# Sheet_MP.net
KiCad netlist of a schematic drawn in Altium Designer
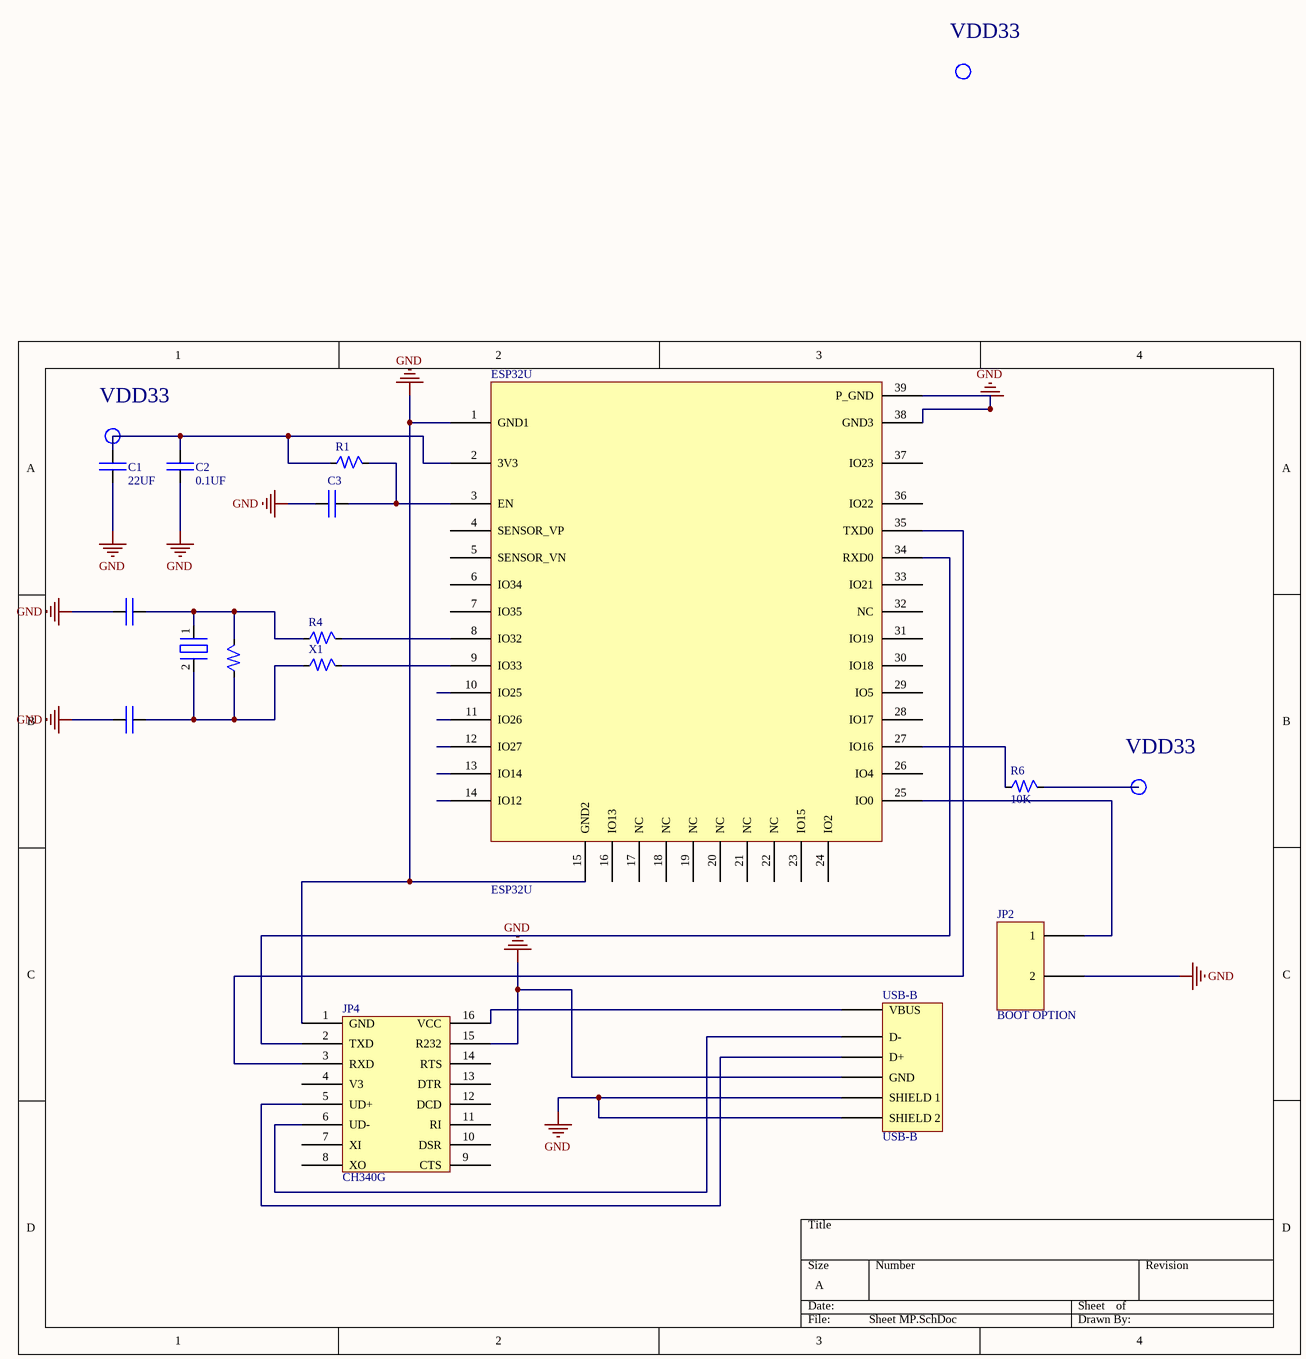
[diagram p0: Sheet MP.SchDoc]

(export (version "E")
  (design (tool "Eeschema 10.0.6"))
  (components
    (comp (ref "C1")
      (value "22UF")
      (footprint "Capacitor")
      (fields (field (name "MANUFACTURER") "PANASONIC") (field (name "MANUFACTURER PART") "EEHZA1V470P"))
      (libsource (lib "SchlibMP") (part "CAP"))
    )
    (comp (ref "C2")
      (value "0.1UF")
      (footprint "Capacitor")
      (fields (field (name "MANUFACTURER") "PANASONIC") (field (name "MANUFACTURER PART") "EEHZA1V470P"))
      (libsource (lib "SchlibMP") (part "CAP"))
    )
    (comp (ref "C3")
      (value "CAP")
      (footprint "Capacitor")
      (fields (field (name "MANUFACTURER") "PANASONIC") (field (name "MANUFACTURER PART") "EEHZA1V470P"))
      (libsource (lib "SchlibMP") (part "CAP"))
    )
    (comp (ref "C4")
      (value "CAP")
      (footprint "Capacitor")
      (fields (field (name "MANUFACTURER") "PANASONIC") (field (name "MANUFACTURER PART") "EEHZA1V470P"))
      (libsource (lib "SchlibMP") (part "CAP"))
    )
    (comp (ref "C5")
      (value "CAP")
      (footprint "Capacitor")
      (fields (field (name "MANUFACTURER") "PANASONIC") (field (name "MANUFACTURER PART") "EEHZA1V470P"))
      (libsource (lib "SchlibMP") (part "CAP"))
    )
    (comp (ref "ESP32U")
      (value "ESP32U")
      (footprint "ESP32U")
      (fields (field (name "MANUFACTURER") "Ai-Thinker") (field (name "MANUFACTURER PART") "ESP32-S"))
      (libsource (lib "SchlibMP") (part "ESP32U"))
    )
    (comp (ref "JP2")
      (value "BOOT OPTION")
      (footprint "HEADER 2 PINS - duplicate")
      (fields
        (field (name "MANUFACTURER") "JST Sales America Inc.")
        (field (name "MANUFACTURER PART") "B2B-XH-A")
      )
      (libsource (lib "SchlibMP") (part "HEADER 2 PINS"))
    )
    (comp (ref "JP4")
      (value "CH340G")
      (footprint "CH340G - duplicate1")
      (fields (field (name "MANUFACTURER") "WCH"))
      (libsource (lib "SchlibMP") (part "CH340G"))
    )
    (comp (ref "R1")
      (value "0805")
      (footprint "Resistor")
      (fields (field (name "MANUFACTURER") "YAGEO") (field (name "MANUFACTURER PART") "RC0805FR-0710KL"))
      (libsource (lib "SchlibMP") (part "0805"))
    )
    (comp (ref "R4")
      (value "0805")
      (footprint "Resistor")
      (fields (field (name "MANUFACTURER") "YAGEO") (field (name "MANUFACTURER PART") "RC0805FR-0710KL"))
      (libsource (lib "SchlibMP") (part "0805"))
    )
    (comp (ref "R5")
      (value "0805")
      (footprint "Resistor")
      (fields (field (name "MANUFACTURER") "YAGEO") (field (name "MANUFACTURER PART") "RC0805FR-0710KL"))
      (libsource (lib "SchlibMP") (part "0805"))
    )
    (comp (ref "R6")
      (value "10K")
      (footprint "Resistor")
      (fields (field (name "MANUFACTURER") "YAGEO") (field (name "MANUFACTURER PART") "RC0805FR-0710KL"))
      (libsource (lib "SchlibMP") (part "0805"))
    )
    (comp (ref "T1")
      (value "CRYSTAL")
      (footprint "CRYSTAL")
      (fields (field (name "MANUFACTURER") "EPSON") (field (name "MANUFACTURER PART") "Q13FC13500004"))
      (libsource (lib "SchlibMP") (part "CRYSTAL"))
    )
    (comp (ref "USB-B")
      (value "USB-B")
      (footprint "USB-B - duplicate1")
      (fields (field (name "MANUFACTURER") "Switchcraft Inc.") (field (name "MANUFACTURER PART") "RAHUB20"))
      (libsource (lib "SchlibMP") (part "USB-B"))
    )
    (comp (ref "X1")
      (value "0805")
      (footprint "Resistor")
      (fields (field (name "MANUFACTURER") "YAGEO") (field (name "MANUFACTURER PART") "RC0805FR-0710KL"))
      (libsource (lib "SchlibMP") (part "0805"))
    )
  )
  (nets
    (net (code "1") (name "GND") (class "Default")
      (node (ref "C1") (pin "1") (pinfunction "1_1") (pintype "passive"))
      (node (ref "C2") (pin "1") (pinfunction "1_1") (pintype "passive"))
      (node (ref "C3") (pin "2") (pinfunction "2_2") (pintype "passive"))
      (node (ref "C4") (pin "2") (pinfunction "2_2") (pintype "passive"))
      (node (ref "C5") (pin "2") (pinfunction "2_2") (pintype "passive"))
      (node (ref "ESP32U") (pin "1") (pinfunction "GND1_1") (pintype "passive"))
      (node (ref "ESP32U") (pin "15") (pinfunction "GND2_15") (pintype "passive"))
      (node (ref "ESP32U") (pin "38") (pinfunction "GND3_38") (pintype "passive"))
      (node (ref "ESP32U") (pin "39") (pinfunction "P_GND_39") (pintype "passive"))
      (node (ref "JP2") (pin "2") (pinfunction "2_2") (pintype "passive"))
      (node (ref "JP4") (pin "1") (pinfunction "GND_1") (pintype "passive"))
      (node (ref "JP4") (pin "15") (pinfunction "R232_15") (pintype "passive"))
      (node (ref "USB-B") (pin "4") (pinfunction "GND_4") (pintype "passive"))
      (node (ref "USB-B") (pin "5") (pinfunction "SHIELD_1_5") (pintype "passive"))
      (node (ref "USB-B") (pin "6") (pinfunction "SHIELD_2_6") (pintype "passive"))
    )
    (net (code "2") (name "Net-(C4-Pad1)") (class "Default")
      (node (ref "C4") (pin "1") (pinfunction "1_1") (pintype "passive"))
      (node (ref "R5") (pin "1") (pinfunction "1_1") (pintype "passive"))
      (node (ref "T1") (pin "2") (pinfunction "2_2") (pintype "passive"))
      (node (ref "X1") (pin "1") (pinfunction "1_1") (pintype "passive"))
    )
    (net (code "3") (name "Net-(C5-Pad1)") (class "Default")
      (node (ref "C5") (pin "1") (pinfunction "1_1") (pintype "passive"))
      (node (ref "R4") (pin "1") (pinfunction "1_1") (pintype "passive"))
      (node (ref "R5") (pin "2") (pinfunction "2_2") (pintype "passive"))
      (node (ref "T1") (pin "1") (pinfunction "1_1") (pintype "passive"))
    )
    (net (code "4") (name "Net-(ESP32U-3V3)") (class "Default")
      (node (ref "C1") (pin "2") (pinfunction "2_2") (pintype "passive"))
      (node (ref "C2") (pin "2") (pinfunction "2_2") (pintype "passive"))
      (node (ref "ESP32U") (pin "2") (pinfunction "3V3_2") (pintype "passive"))
      (node (ref "R1") (pin "1") (pinfunction "1_1") (pintype "passive"))
    )
    (net (code "5") (name "Net-(ESP32U-EN)") (class "Default")
      (node (ref "C3") (pin "1") (pinfunction "1_1") (pintype "passive"))
      (node (ref "ESP32U") (pin "3") (pinfunction "EN_3") (pintype "passive"))
      (node (ref "R1") (pin "2") (pinfunction "2_2") (pintype "passive"))
    )
    (net (code "6") (name "Net-(ESP32U-IO0)") (class "Default")
      (node (ref "ESP32U") (pin "25") (pinfunction "IO0_25") (pintype "passive"))
      (node (ref "JP2") (pin "1") (pinfunction "1_1") (pintype "passive"))
    )
    (net (code "7") (name "Net-(ESP32U-IO16)") (class "Default")
      (node (ref "ESP32U") (pin "27") (pinfunction "IO16_27") (pintype "passive"))
      (node (ref "R6") (pin "1") (pinfunction "1_1") (pintype "passive"))
    )
    (net (code "8") (name "Net-(ESP32U-IO32)") (class "Default")
      (node (ref "ESP32U") (pin "8") (pinfunction "IO32_8") (pintype "passive"))
      (node (ref "R4") (pin "2") (pinfunction "2_2") (pintype "passive"))
    )
    (net (code "9") (name "Net-(ESP32U-IO33)") (class "Default")
      (node (ref "ESP32U") (pin "9") (pinfunction "IO33_9") (pintype "passive"))
      (node (ref "X1") (pin "2") (pinfunction "2_2") (pintype "passive"))
    )
    (net (code "10") (name "Net-(ESP32U-RXD0)") (class "Default")
      (node (ref "ESP32U") (pin "34") (pinfunction "RXD0_34") (pintype "passive"))
      (node (ref "JP4") (pin "2") (pinfunction "TXD_2") (pintype "passive"))
    )
    (net (code "11") (name "Net-(ESP32U-TXD0)") (class "Default")
      (node (ref "ESP32U") (pin "35") (pinfunction "TXD0_35") (pintype "passive"))
      (node (ref "JP4") (pin "3") (pinfunction "RXD_3") (pintype "passive"))
    )
    (net (code "12") (name "Net-(JP4-UD+)") (class "Default")
      (node (ref "JP4") (pin "5") (pinfunction "UD+_5") (pintype "passive"))
      (node (ref "USB-B") (pin "3") (pinfunction "D+_3") (pintype "passive"))
    )
    (net (code "13") (name "Net-(JP4-UD-)") (class "Default")
      (node (ref "JP4") (pin "6") (pinfunction "UD-_6") (pintype "passive"))
      (node (ref "USB-B") (pin "2") (pinfunction "D-_2") (pintype "passive"))
    )
    (net (code "14") (name "Net-(JP4-VCC)") (class "Default")
      (node (ref "JP4") (pin "16") (pinfunction "VCC_16") (pintype "passive"))
      (node (ref "USB-B") (pin "1") (pinfunction "VBUS_1") (pintype "passive"))
    )
    (net (code "15") (name "unconnected-(ESP32U-IO2-Pad24)") (class "Default")
      (node (ref "ESP32U") (pin "24") (pinfunction "IO2_24") (pintype "passive"))
    )
    (net (code "16") (name "unconnected-(ESP32U-IO4-Pad26)") (class "Default")
      (node (ref "ESP32U") (pin "26") (pinfunction "IO4_26") (pintype "passive"))
    )
    (net (code "17") (name "unconnected-(ESP32U-IO5-Pad29)") (class "Default")
      (node (ref "ESP32U") (pin "29") (pinfunction "IO5_29") (pintype "passive"))
    )
    (net (code "18") (name "unconnected-(ESP32U-IO12-Pad14)") (class "Default")
      (node (ref "ESP32U") (pin "14") (pinfunction "IO12_14") (pintype "passive"))
    )
    (net (code "19") (name "unconnected-(ESP32U-IO13-Pad16)") (class "Default")
      (node (ref "ESP32U") (pin "16") (pinfunction "IO13_16") (pintype "passive"))
    )
    (net (code "20") (name "unconnected-(ESP32U-IO14-Pad13)") (class "Default")
      (node (ref "ESP32U") (pin "13") (pinfunction "IO14_13") (pintype "passive"))
    )
    (net (code "21") (name "unconnected-(ESP32U-IO15-Pad23)") (class "Default")
      (node (ref "ESP32U") (pin "23") (pinfunction "IO15_23") (pintype "passive"))
    )
    (net (code "22") (name "unconnected-(ESP32U-IO17-Pad28)") (class "Default")
      (node (ref "ESP32U") (pin "28") (pinfunction "IO17_28") (pintype "passive"))
    )
    (net (code "23") (name "unconnected-(ESP32U-IO18-Pad30)") (class "Default")
      (node (ref "ESP32U") (pin "30") (pinfunction "IO18_30") (pintype "passive"))
    )
    (net (code "24") (name "unconnected-(ESP32U-IO19-Pad31)") (class "Default")
      (node (ref "ESP32U") (pin "31") (pinfunction "IO19_31") (pintype "passive"))
    )
    (net (code "25") (name "unconnected-(ESP32U-IO21-Pad33)") (class "Default")
      (node (ref "ESP32U") (pin "33") (pinfunction "IO21_33") (pintype "passive"))
    )
    (net (code "26") (name "unconnected-(ESP32U-IO22-Pad36)") (class "Default")
      (node (ref "ESP32U") (pin "36") (pinfunction "IO22_36") (pintype "passive"))
    )
    (net (code "27") (name "unconnected-(ESP32U-IO23-Pad37)") (class "Default")
      (node (ref "ESP32U") (pin "37") (pinfunction "IO23_37") (pintype "passive"))
    )
    (net (code "28") (name "unconnected-(ESP32U-IO25-Pad10)") (class "Default")
      (node (ref "ESP32U") (pin "10") (pinfunction "IO25_10") (pintype "passive"))
    )
    (net (code "29") (name "unconnected-(ESP32U-IO26-Pad11)") (class "Default")
      (node (ref "ESP32U") (pin "11") (pinfunction "IO26_11") (pintype "passive"))
    )
    (net (code "30") (name "unconnected-(ESP32U-IO27-Pad12)") (class "Default")
      (node (ref "ESP32U") (pin "12") (pinfunction "IO27_12") (pintype "passive"))
    )
    (net (code "31") (name "unconnected-(ESP32U-IO34-Pad6)") (class "Default")
      (node (ref "ESP32U") (pin "6") (pinfunction "IO34_6") (pintype "passive"))
    )
    (net (code "32") (name "unconnected-(ESP32U-IO35-Pad7)") (class "Default")
      (node (ref "ESP32U") (pin "7") (pinfunction "IO35_7") (pintype "passive"))
    )
    (net (code "33") (name "unconnected-(ESP32U-NC-Pad17)") (class "Default")
      (node (ref "ESP32U") (pin "17") (pinfunction "NC_17") (pintype "passive"))
    )
    (net (code "34") (name "unconnected-(ESP32U-NC-Pad18)") (class "Default")
      (node (ref "ESP32U") (pin "18") (pinfunction "NC_18") (pintype "passive"))
    )
    (net (code "35") (name "unconnected-(ESP32U-NC-Pad19)") (class "Default")
      (node (ref "ESP32U") (pin "19") (pinfunction "NC_19") (pintype "passive"))
    )
    (net (code "36") (name "unconnected-(ESP32U-NC-Pad20)") (class "Default")
      (node (ref "ESP32U") (pin "20") (pinfunction "NC_20") (pintype "passive"))
    )
    (net (code "37") (name "unconnected-(ESP32U-NC-Pad21)") (class "Default")
      (node (ref "ESP32U") (pin "21") (pinfunction "NC_21") (pintype "passive"))
    )
    (net (code "38") (name "unconnected-(ESP32U-NC-Pad22)") (class "Default")
      (node (ref "ESP32U") (pin "22") (pinfunction "NC_22") (pintype "passive"))
    )
    (net (code "39") (name "unconnected-(ESP32U-NC-Pad32)") (class "Default")
      (node (ref "ESP32U") (pin "32") (pinfunction "NC_32") (pintype "passive"))
    )
    (net (code "40") (name "unconnected-(ESP32U-SENSOR_VN-Pad5)") (class "Default")
      (node (ref "ESP32U") (pin "5") (pinfunction "SENSOR_VN_5") (pintype "passive"))
    )
    (net (code "41") (name "unconnected-(ESP32U-SENSOR_VP-Pad4)") (class "Default")
      (node (ref "ESP32U") (pin "4") (pinfunction "SENSOR_VP_4") (pintype "passive"))
    )
    (net (code "42") (name "unconnected-(JP4-CTS-Pad9)") (class "Default")
      (node (ref "JP4") (pin "9") (pinfunction "CTS_9") (pintype "passive"))
    )
    (net (code "43") (name "unconnected-(JP4-DCD-Pad12)") (class "Default")
      (node (ref "JP4") (pin "12") (pinfunction "DCD_12") (pintype "passive"))
    )
    (net (code "44") (name "unconnected-(JP4-DSR-Pad10)") (class "Default")
      (node (ref "JP4") (pin "10") (pinfunction "DSR_10") (pintype "passive"))
    )
    (net (code "45") (name "unconnected-(JP4-DTR-Pad13)") (class "Default")
      (node (ref "JP4") (pin "13") (pinfunction "DTR_13") (pintype "passive"))
    )
    (net (code "46") (name "unconnected-(JP4-RI-Pad11)") (class "Default")
      (node (ref "JP4") (pin "11") (pinfunction "RI_11") (pintype "passive"))
    )
    (net (code "47") (name "unconnected-(JP4-RTS-Pad14)") (class "Default")
      (node (ref "JP4") (pin "14") (pinfunction "RTS_14") (pintype "passive"))
    )
    (net (code "48") (name "unconnected-(JP4-V3-Pad4)") (class "Default")
      (node (ref "JP4") (pin "4") (pinfunction "V3_4") (pintype "passive"))
    )
    (net (code "49") (name "unconnected-(JP4-XI-Pad7)") (class "Default")
      (node (ref "JP4") (pin "7") (pinfunction "XI_7") (pintype "passive"))
    )
    (net (code "50") (name "unconnected-(JP4-XO-Pad8)") (class "Default")
      (node (ref "JP4") (pin "8") (pinfunction "XO_8") (pintype "passive"))
    )
    (net (code "51") (name "unconnected-(R6-Pad2)") (class "Default")
      (node (ref "R6") (pin "2") (pinfunction "2_2") (pintype "passive"))
    )
  )
)
